# PWM_PPM_FMU3_REV_E.net
KiCad netlist of a schematic drawn in Altium Designer
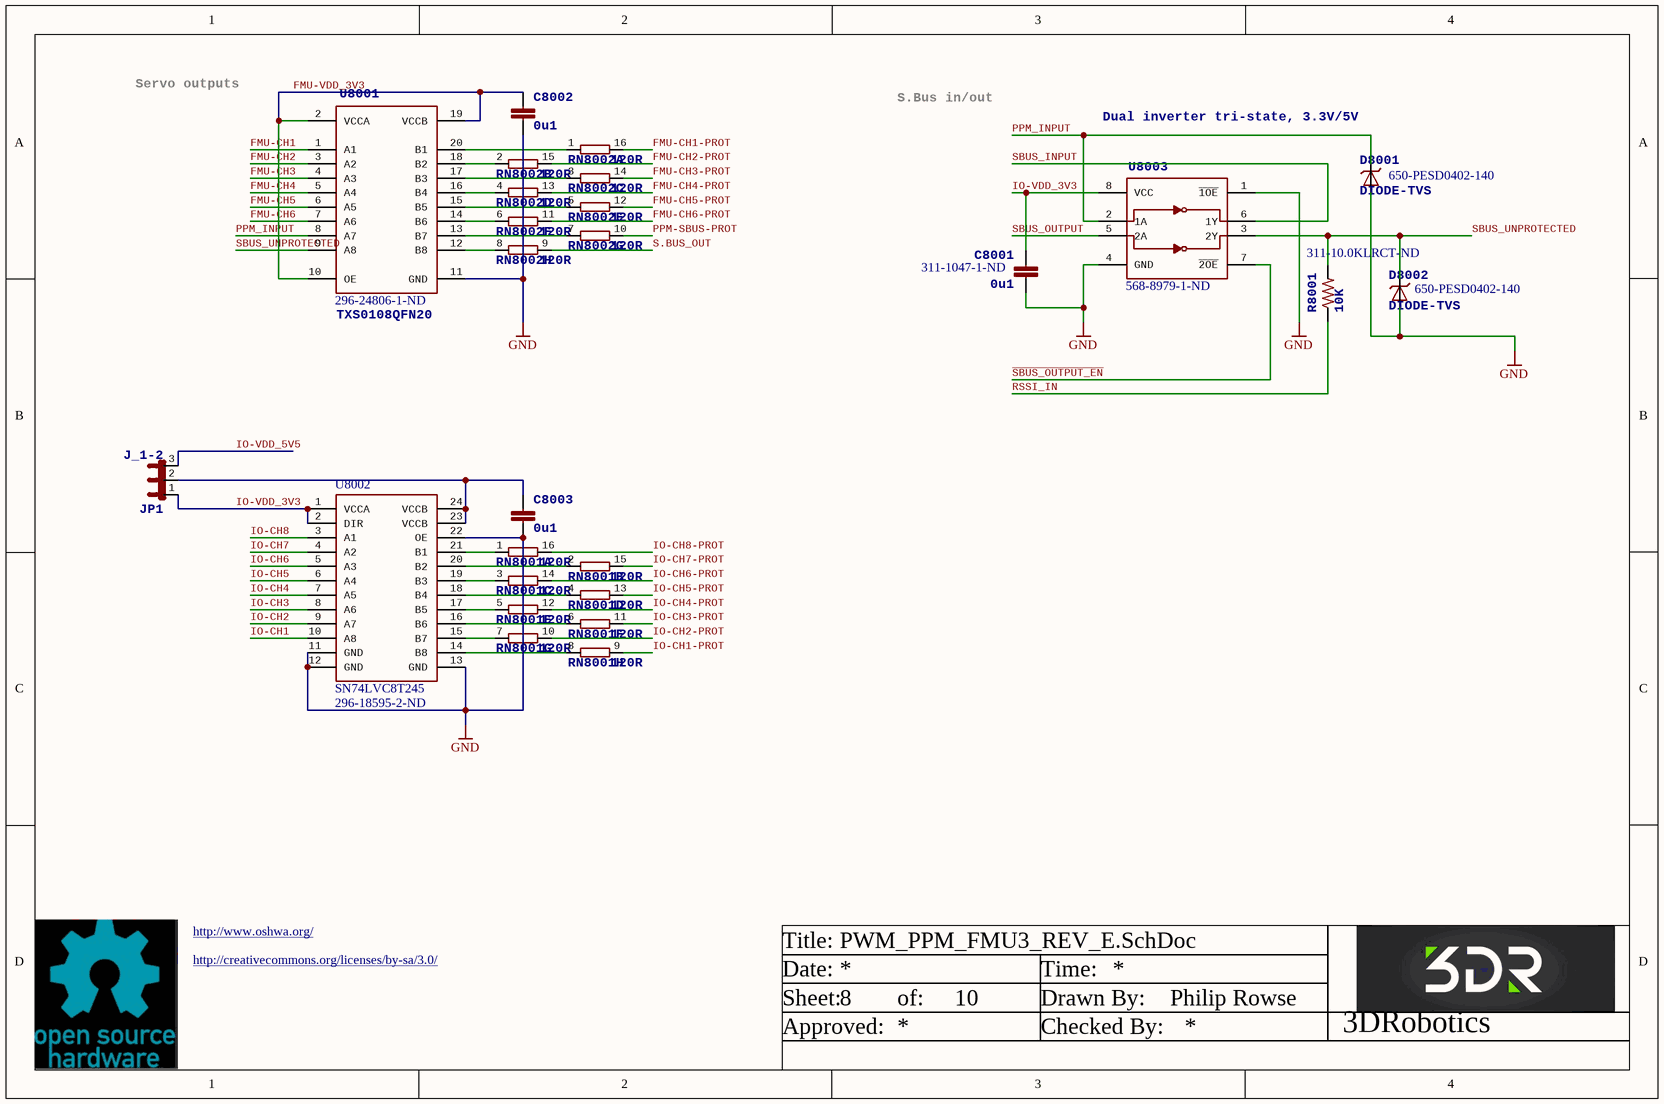
[diagram p0: PWM_PPM_FMU3_REV_E.SchDoc]

(export (version "E")
  (design (tool "Eeschema 10.0.6"))
  (components
    (comp (ref "C8001")
      (value "0u1")
      (footprint "0402-CAP")
      (description "CAP CER 0.1UF 16V Y5V 0402")
      (fields
        (field (name "PARTNO") "CC0402ZRY5V7BB104")
        (field (name "SUPPLIER PART NUMBER 1") "311-1047-1-ND")
        (field (name "3DR_PARTNO") "ECM0700")
      )
      (libsource (lib "") (part "CAP0402_1"))
    )
    (comp (ref "C8002")
      (value "0u1")
      (footprint "0402-CAP")
      (description "CAP CER 0.1UF 16V Y5V 0402")
      (fields (field (name "PARTNO") "CC0402ZRY5V7BB104") (field (name "3DR_PARTNO") "ECM0700"))
      (libsource (lib "pixhawk2") (part "CAP0402"))
    )
    (comp (ref "C8003")
      (value "0u1")
      (footprint "0402-CAP")
      (description "CAP CER 0.1UF 16V Y5V 0402")
      (fields (field (name "PARTNO") "CC0402ZRY5V7BB104") (field (name "3DR_PARTNO") "ECM0700"))
      (libsource (lib "pixhawk2") (part "CAP0402"))
    )
    (comp (ref "D8001")
      (value "DIODE-TVS")
      (footprint "0402-TVS")
      (description "TVS DIODE 14VWM 40VC 0402")
      (fields
        (field (name "SUPPLIER PART NUMBER 1") "650-PESD0402-140")
        (field (name "3DR_PARTNO") "ECM0837")
        (field (name "PARTNO") "PESD0402-140")
      )
      (libsource (lib "pixhawk2") (part "DIODE-TVS"))
    )
    (comp (ref "D8002")
      (value "DIODE-TVS")
      (footprint "0402-TVS")
      (description "TVS DIODE 14VWM 40VC 0402")
      (fields
        (field (name "SUPPLIER PART NUMBER 1") "650-PESD0402-140")
        (field (name "3DR_PARTNO") "ECM0837")
        (field (name "PARTNO") "PESD0402-140")
      )
      (libsource (lib "pixhawk2") (part "DIODE-TVS"))
    )
    (comp (ref "JP1")
      (value "J_1-2")
      (footprint "SJ_3_NO_PLACE_1-2_short")
      (libsource (lib "3DR") (part "JUMPER-31-2"))
    )
    (comp (ref "R8001")
      (value "10K")
      (footprint "0402-RES")
      (description "RES 10K OHM 1/16W 1% 0402 SMD")
      (fields
        (field (name "PARTNO") "RC0402FR-0710KL")
        (field (name "SUPPLIER PART NUMBER 1") "311-10.0KLRCT-ND")
        (field (name "3DR_PARTNO") "ECM0800")
      )
      (libsource (lib "pixhawk2") (part "RESISTOR0402-RES"))
    )
    (comp (ref "RN8001")
      (value "120R")
      (footprint "EXB2HV")
      (description "RES ARRAY 120 OHM 8 RES 1506")
      (fields (field (name "PARTNO") "EXB-2HV121JV") (field (name "3DR_PARTNO") "ECM0266"))
      (libsource (lib "pixhawk2") (part "8R-NEXB2HV-220R"))
    )
    (comp (ref "RN8002")
      (value "120R")
      (footprint "EXB2HV")
      (description "RES ARRAY 120 OHM 8 RES 1506")
      (fields (field (name "PARTNO") "EXB-2HV121JV") (field (name "3DR_PARTNO") "ECM0266"))
      (libsource (lib "pixhawk2") (part "8R-NEXB2HV-220R"))
    )
    (comp (ref "U8001")
      (value "TXS0108QFN20")
      (footprint "QFN20-RGY")
      (description "IC XLATR VOLT-LVL 8B BDIR 20QFN")
      (fields
        (field (name "SUPPLIER PART NUMBER 1") "296-24806-1-ND")
        (field (name "3DR_PARTNO") "ECM0845")
        (field (name "PARTNO") "TXS0108ERGYR")
      )
      (libsource (lib "pixhawk2") (part "TXS0108QFN20"))
    )
    (comp (ref "U8002")
      (value "SN74LVC8T245")
      (footprint "QFN24-RGY")
      (fields (field (name "SUPPLIER PART NUMBER 1") "296-18595-2-ND"))
      (libsource (lib "3DR") (part "SN74LVC8T245"))
    )
    (comp (ref "U8003")
      (value "Dual inverter tri-state, 3.3V/5V")
      (footprint "TSSOP8_SOT505-2")
      (description "IC INVERTER DUAL 4-INPUT 8TSSOP")
      (fields
        (field (name "SUPPLIER PART NUMBER 1") "568-8979-1-ND")
        (field (name "3DR_PARTNO") "ECM0817")
        (field (name "PARTNO") "74LVC2G240DP,125")
      )
      (libsource (lib "pixhawk2") (part "74LVC2G240-TSSOP-8"))
    )
  )
  (nets
    (net (code "1") (name "/FMU-CH1") (class "Default")
      (node (ref "U8001") (pin "1") (pinfunction "A1_1") (pintype "passive"))
    )
    (net (code "2") (name "/FMU-CH1-PROT") (class "Default")
      (node (ref "RN8002") (pin "16") (pinfunction "2_16") (pintype "passive"))
    )
    (net (code "3") (name "/FMU-CH2") (class "Default")
      (node (ref "U8001") (pin "3") (pinfunction "A2_3") (pintype "passive"))
    )
    (net (code "4") (name "/FMU-CH2-PROT") (class "Default")
      (node (ref "RN8002") (pin "15") (pinfunction "2_15") (pintype "passive"))
    )
    (net (code "5") (name "/FMU-CH3") (class "Default")
      (node (ref "U8001") (pin "4") (pinfunction "A3_4") (pintype "passive"))
    )
    (net (code "6") (name "/FMU-CH3-PROT") (class "Default")
      (node (ref "RN8002") (pin "14") (pinfunction "2_14") (pintype "passive"))
    )
    (net (code "7") (name "/FMU-CH4") (class "Default")
      (node (ref "U8001") (pin "5") (pinfunction "A4_5") (pintype "passive"))
    )
    (net (code "8") (name "/FMU-CH4-PROT") (class "Default")
      (node (ref "RN8002") (pin "13") (pinfunction "2_13") (pintype "passive"))
    )
    (net (code "9") (name "/FMU-CH5") (class "Default")
      (node (ref "U8001") (pin "6") (pinfunction "A5_6") (pintype "passive"))
    )
    (net (code "10") (name "/FMU-CH5-PROT") (class "Default")
      (node (ref "RN8002") (pin "12") (pinfunction "2_12") (pintype "passive"))
    )
    (net (code "11") (name "/FMU-CH6") (class "Default")
      (node (ref "U8001") (pin "7") (pinfunction "A6_7") (pintype "passive"))
    )
    (net (code "12") (name "/FMU-CH6-PROT") (class "Default")
      (node (ref "RN8002") (pin "11") (pinfunction "2_11") (pintype "passive"))
    )
    (net (code "13") (name "/FMU-VDD_3V3") (class "Default")
      (node (ref "C8002") (pin "P$1") (pinfunction "1_P$1") (pintype "passive"))
      (node (ref "U8001") (pin "10") (pinfunction "OE_10") (pintype "passive"))
      (node (ref "U8001") (pin "19") (pinfunction "VCCB_19") (pintype "passive"))
      (node (ref "U8001") (pin "2") (pinfunction "VCCA_2") (pintype "passive"))
    )
    (net (code "14") (name "/IO-CH1") (class "Default")
      (node (ref "U8002") (pin "10") (pinfunction "A8_10") (pintype "passive"))
    )
    (net (code "15") (name "/IO-CH1-PROT") (class "Default")
      (node (ref "RN8001") (pin "9") (pinfunction "2_9") (pintype "passive"))
    )
    (net (code "16") (name "/IO-CH2") (class "Default")
      (node (ref "U8002") (pin "9") (pinfunction "A7_9") (pintype "passive"))
    )
    (net (code "17") (name "/IO-CH2-PROT") (class "Default")
      (node (ref "RN8001") (pin "10") (pinfunction "2_10") (pintype "passive"))
    )
    (net (code "18") (name "/IO-CH3") (class "Default")
      (node (ref "U8002") (pin "8") (pinfunction "A6_8") (pintype "passive"))
    )
    (net (code "19") (name "/IO-CH3-PROT") (class "Default")
      (node (ref "RN8001") (pin "11") (pinfunction "2_11") (pintype "passive"))
    )
    (net (code "20") (name "/IO-CH4") (class "Default")
      (node (ref "U8002") (pin "7") (pinfunction "A5_7") (pintype "passive"))
    )
    (net (code "21") (name "/IO-CH4-PROT") (class "Default")
      (node (ref "RN8001") (pin "12") (pinfunction "2_12") (pintype "passive"))
    )
    (net (code "22") (name "/IO-CH5") (class "Default")
      (node (ref "U8002") (pin "6") (pinfunction "A4_6") (pintype "passive"))
    )
    (net (code "23") (name "/IO-CH5-PROT") (class "Default")
      (node (ref "RN8001") (pin "13") (pinfunction "2_13") (pintype "passive"))
    )
    (net (code "24") (name "/IO-CH6") (class "Default")
      (node (ref "U8002") (pin "5") (pinfunction "A3_5") (pintype "passive"))
    )
    (net (code "25") (name "/IO-CH6-PROT") (class "Default")
      (node (ref "RN8001") (pin "14") (pinfunction "2_14") (pintype "passive"))
    )
    (net (code "26") (name "/IO-CH7") (class "Default")
      (node (ref "U8002") (pin "4") (pinfunction "A2_4") (pintype "passive"))
    )
    (net (code "27") (name "/IO-CH7-PROT") (class "Default")
      (node (ref "RN8001") (pin "15") (pinfunction "2_15") (pintype "passive"))
    )
    (net (code "28") (name "/IO-CH8") (class "Default")
      (node (ref "U8002") (pin "3") (pinfunction "A1_3") (pintype "passive"))
    )
    (net (code "29") (name "/IO-CH8-PROT") (class "Default")
      (node (ref "RN8001") (pin "16") (pinfunction "2_16") (pintype "passive"))
    )
    (net (code "30") (name "/IO-VDD_3V3") (class "Default")
      (node (ref "C8001") (pin "P$1") (pinfunction "1_P$1") (pintype "passive"))
      (node (ref "JP1") (pin "1") (pinfunction "1_1") (pintype "passive"))
      (node (ref "U8002") (pin "1") (pinfunction "VCCA_1") (pintype "passive"))
      (node (ref "U8002") (pin "2") (pinfunction "DIR_2") (pintype "passive"))
      (node (ref "U8003") (pin "8") (pinfunction "VCC_8") (pintype "open_emitter"))
    )
    (net (code "31") (name "/IO-VDD_5V5") (class "Default")
      (node (ref "JP1") (pin "3") (pinfunction "3_3") (pintype "passive"))
    )
    (net (code "32") (name "/PPM-SBUS-PROT") (class "Default")
      (node (ref "RN8002") (pin "10") (pinfunction "2_10") (pintype "passive"))
    )
    (net (code "33") (name "/PPM_INPUT") (class "Default")
      (node (ref "D8001") (pin "C") (pinfunction "C_C") (pintype "passive"))
      (node (ref "U8001") (pin "8") (pinfunction "A7_8") (pintype "passive"))
      (node (ref "U8003") (pin "2") (pinfunction "1A_2") (pintype "passive"))
    )
    (net (code "34") (name "/RSSI_IN") (class "Default")
      (node (ref "R8001") (pin "P$1") (pinfunction "1_P$1") (pintype "passive"))
    )
    (net (code "35") (name "/S.BUS_OUT") (class "Default")
      (node (ref "RN8002") (pin "9") (pinfunction "2_9") (pintype "passive"))
    )
    (net (code "36") (name "/SBUS_INPUT") (class "Default")
      (node (ref "U8003") (pin "6") (pinfunction "1Y_6") (pintype "passive"))
    )
    (net (code "37") (name "/SBUS_OUTPUT") (class "Default")
      (node (ref "U8003") (pin "5") (pinfunction "2A_5") (pintype "passive"))
    )
    (net (code "38") (name "/SBUS_UNPROTECTED") (class "Default")
      (node (ref "D8002") (pin "C") (pinfunction "C_C") (pintype "passive"))
      (node (ref "R8001") (pin "P$2") (pinfunction "2_P$2") (pintype "passive"))
      (node (ref "U8001") (pin "9") (pinfunction "A8_9") (pintype "passive"))
      (node (ref "U8003") (pin "3") (pinfunction "2Y_3") (pintype "passive"))
    )
    (net (code "39") (name "/~{SBUS_OUTPUT_EN}") (class "Default")
      (node (ref "U8003") (pin "7") (pinfunction "~{2OE}_7") (pintype "passive"))
    )
    (net (code "40") (name "GND") (class "Default")
      (node (ref "C8001") (pin "P$2") (pinfunction "2_P$2") (pintype "passive"))
      (node (ref "C8002") (pin "P$2") (pinfunction "2_P$2") (pintype "passive"))
      (node (ref "C8003") (pin "P$2") (pinfunction "2_P$2") (pintype "passive"))
      (node (ref "D8001") (pin "A") (pinfunction "A_A") (pintype "passive"))
      (node (ref "D8002") (pin "A") (pinfunction "A_A") (pintype "passive"))
      (node (ref "U8001") (pin "11") (pinfunction "GND_11") (pintype "open_emitter"))
      (node (ref "U8002") (pin "11") (pinfunction "GND_11") (pintype "open_emitter"))
      (node (ref "U8002") (pin "12") (pinfunction "GND_12") (pintype "open_emitter"))
      (node (ref "U8002") (pin "13") (pinfunction "GND_13") (pintype "open_emitter"))
      (node (ref "U8002") (pin "22") (pinfunction "OE_22") (pintype "passive"))
      (node (ref "U8003") (pin "1") (pinfunction "~{1OE}_1") (pintype "passive"))
      (node (ref "U8003") (pin "4") (pinfunction "GND_4") (pintype "open_emitter"))
    )
    (net (code "41") (name "Net-(C8003-1)") (class "Default")
      (node (ref "C8003") (pin "P$1") (pinfunction "1_P$1") (pintype "passive"))
      (node (ref "JP1") (pin "2") (pinfunction "2_2") (pintype "passive"))
      (node (ref "U8002") (pin "23") (pinfunction "VCCB_23") (pintype "passive"))
      (node (ref "U8002") (pin "24") (pinfunction "VCCB_24") (pintype "passive"))
    )
    (net (code "42") (name "Net-(RN8001B-1)") (class "Default")
      (node (ref "RN8001") (pin "2") (pinfunction "1_2") (pintype "passive"))
      (node (ref "U8002") (pin "20") (pinfunction "B2_20") (pintype "passive"))
    )
    (net (code "43") (name "Net-(RN8001C-1)") (class "Default")
      (node (ref "RN8001") (pin "3") (pinfunction "1_3") (pintype "passive"))
      (node (ref "U8002") (pin "19") (pinfunction "B3_19") (pintype "passive"))
    )
    (net (code "44") (name "Net-(RN8001D-1)") (class "Default")
      (node (ref "RN8001") (pin "4") (pinfunction "1_4") (pintype "passive"))
      (node (ref "U8002") (pin "18") (pinfunction "B4_18") (pintype "passive"))
    )
    (net (code "45") (name "Net-(RN8001E-1)") (class "Default")
      (node (ref "RN8001") (pin "5") (pinfunction "1_5") (pintype "passive"))
      (node (ref "U8002") (pin "17") (pinfunction "B5_17") (pintype "passive"))
    )
    (net (code "46") (name "Net-(RN8001F-1)") (class "Default")
      (node (ref "RN8001") (pin "6") (pinfunction "1_6") (pintype "passive"))
      (node (ref "U8002") (pin "16") (pinfunction "B6_16") (pintype "passive"))
    )
    (net (code "47") (name "Net-(RN8001G-1)") (class "Default")
      (node (ref "RN8001") (pin "7") (pinfunction "1_7") (pintype "passive"))
      (node (ref "U8002") (pin "15") (pinfunction "B7_15") (pintype "passive"))
    )
    (net (code "48") (name "Net-(RN8001H-1)") (class "Default")
      (node (ref "RN8001") (pin "8") (pinfunction "1_8") (pintype "passive"))
      (node (ref "U8002") (pin "14") (pinfunction "B8_14") (pintype "passive"))
    )
    (net (code "49") (name "Net-(RN8002B-1)") (class "Default")
      (node (ref "RN8002") (pin "2") (pinfunction "1_2") (pintype "passive"))
      (node (ref "U8001") (pin "18") (pinfunction "B2_18") (pintype "passive"))
    )
    (net (code "50") (name "Net-(RN8002C-1)") (class "Default")
      (node (ref "RN8002") (pin "3") (pinfunction "1_3") (pintype "passive"))
      (node (ref "U8001") (pin "17") (pinfunction "B3_17") (pintype "passive"))
    )
    (net (code "51") (name "Net-(RN8002D-1)") (class "Default")
      (node (ref "RN8002") (pin "4") (pinfunction "1_4") (pintype "passive"))
      (node (ref "U8001") (pin "16") (pinfunction "B4_16") (pintype "passive"))
    )
    (net (code "52") (name "Net-(RN8002E-1)") (class "Default")
      (node (ref "RN8002") (pin "5") (pinfunction "1_5") (pintype "passive"))
      (node (ref "U8001") (pin "15") (pinfunction "B5_15") (pintype "passive"))
    )
    (net (code "53") (name "Net-(RN8002F-1)") (class "Default")
      (node (ref "RN8002") (pin "6") (pinfunction "1_6") (pintype "passive"))
      (node (ref "U8001") (pin "14") (pinfunction "B6_14") (pintype "passive"))
    )
    (net (code "54") (name "Net-(RN8002G-1)") (class "Default")
      (node (ref "RN8002") (pin "7") (pinfunction "1_7") (pintype "passive"))
      (node (ref "U8001") (pin "13") (pinfunction "B7_13") (pintype "passive"))
    )
    (net (code "55") (name "Net-(RN8002H-1)") (class "Default")
      (node (ref "RN8002") (pin "8") (pinfunction "1_8") (pintype "passive"))
      (node (ref "U8001") (pin "12") (pinfunction "B8_12") (pintype "passive"))
    )
    (net (code "56") (name "Net-(U8001-B1)") (class "Default")
      (node (ref "RN8002") (pin "1") (pinfunction "1_1") (pintype "passive"))
      (node (ref "U8001") (pin "20") (pinfunction "B1_20") (pintype "passive"))
    )
    (net (code "57") (name "Net-(U8002-B1)") (class "Default")
      (node (ref "RN8001") (pin "1") (pinfunction "1_1") (pintype "passive"))
      (node (ref "U8002") (pin "21") (pinfunction "B1_21") (pintype "passive"))
    )
  )
)
